# untitled.net
KiCad netlist of a schematic drawn in EAGLE
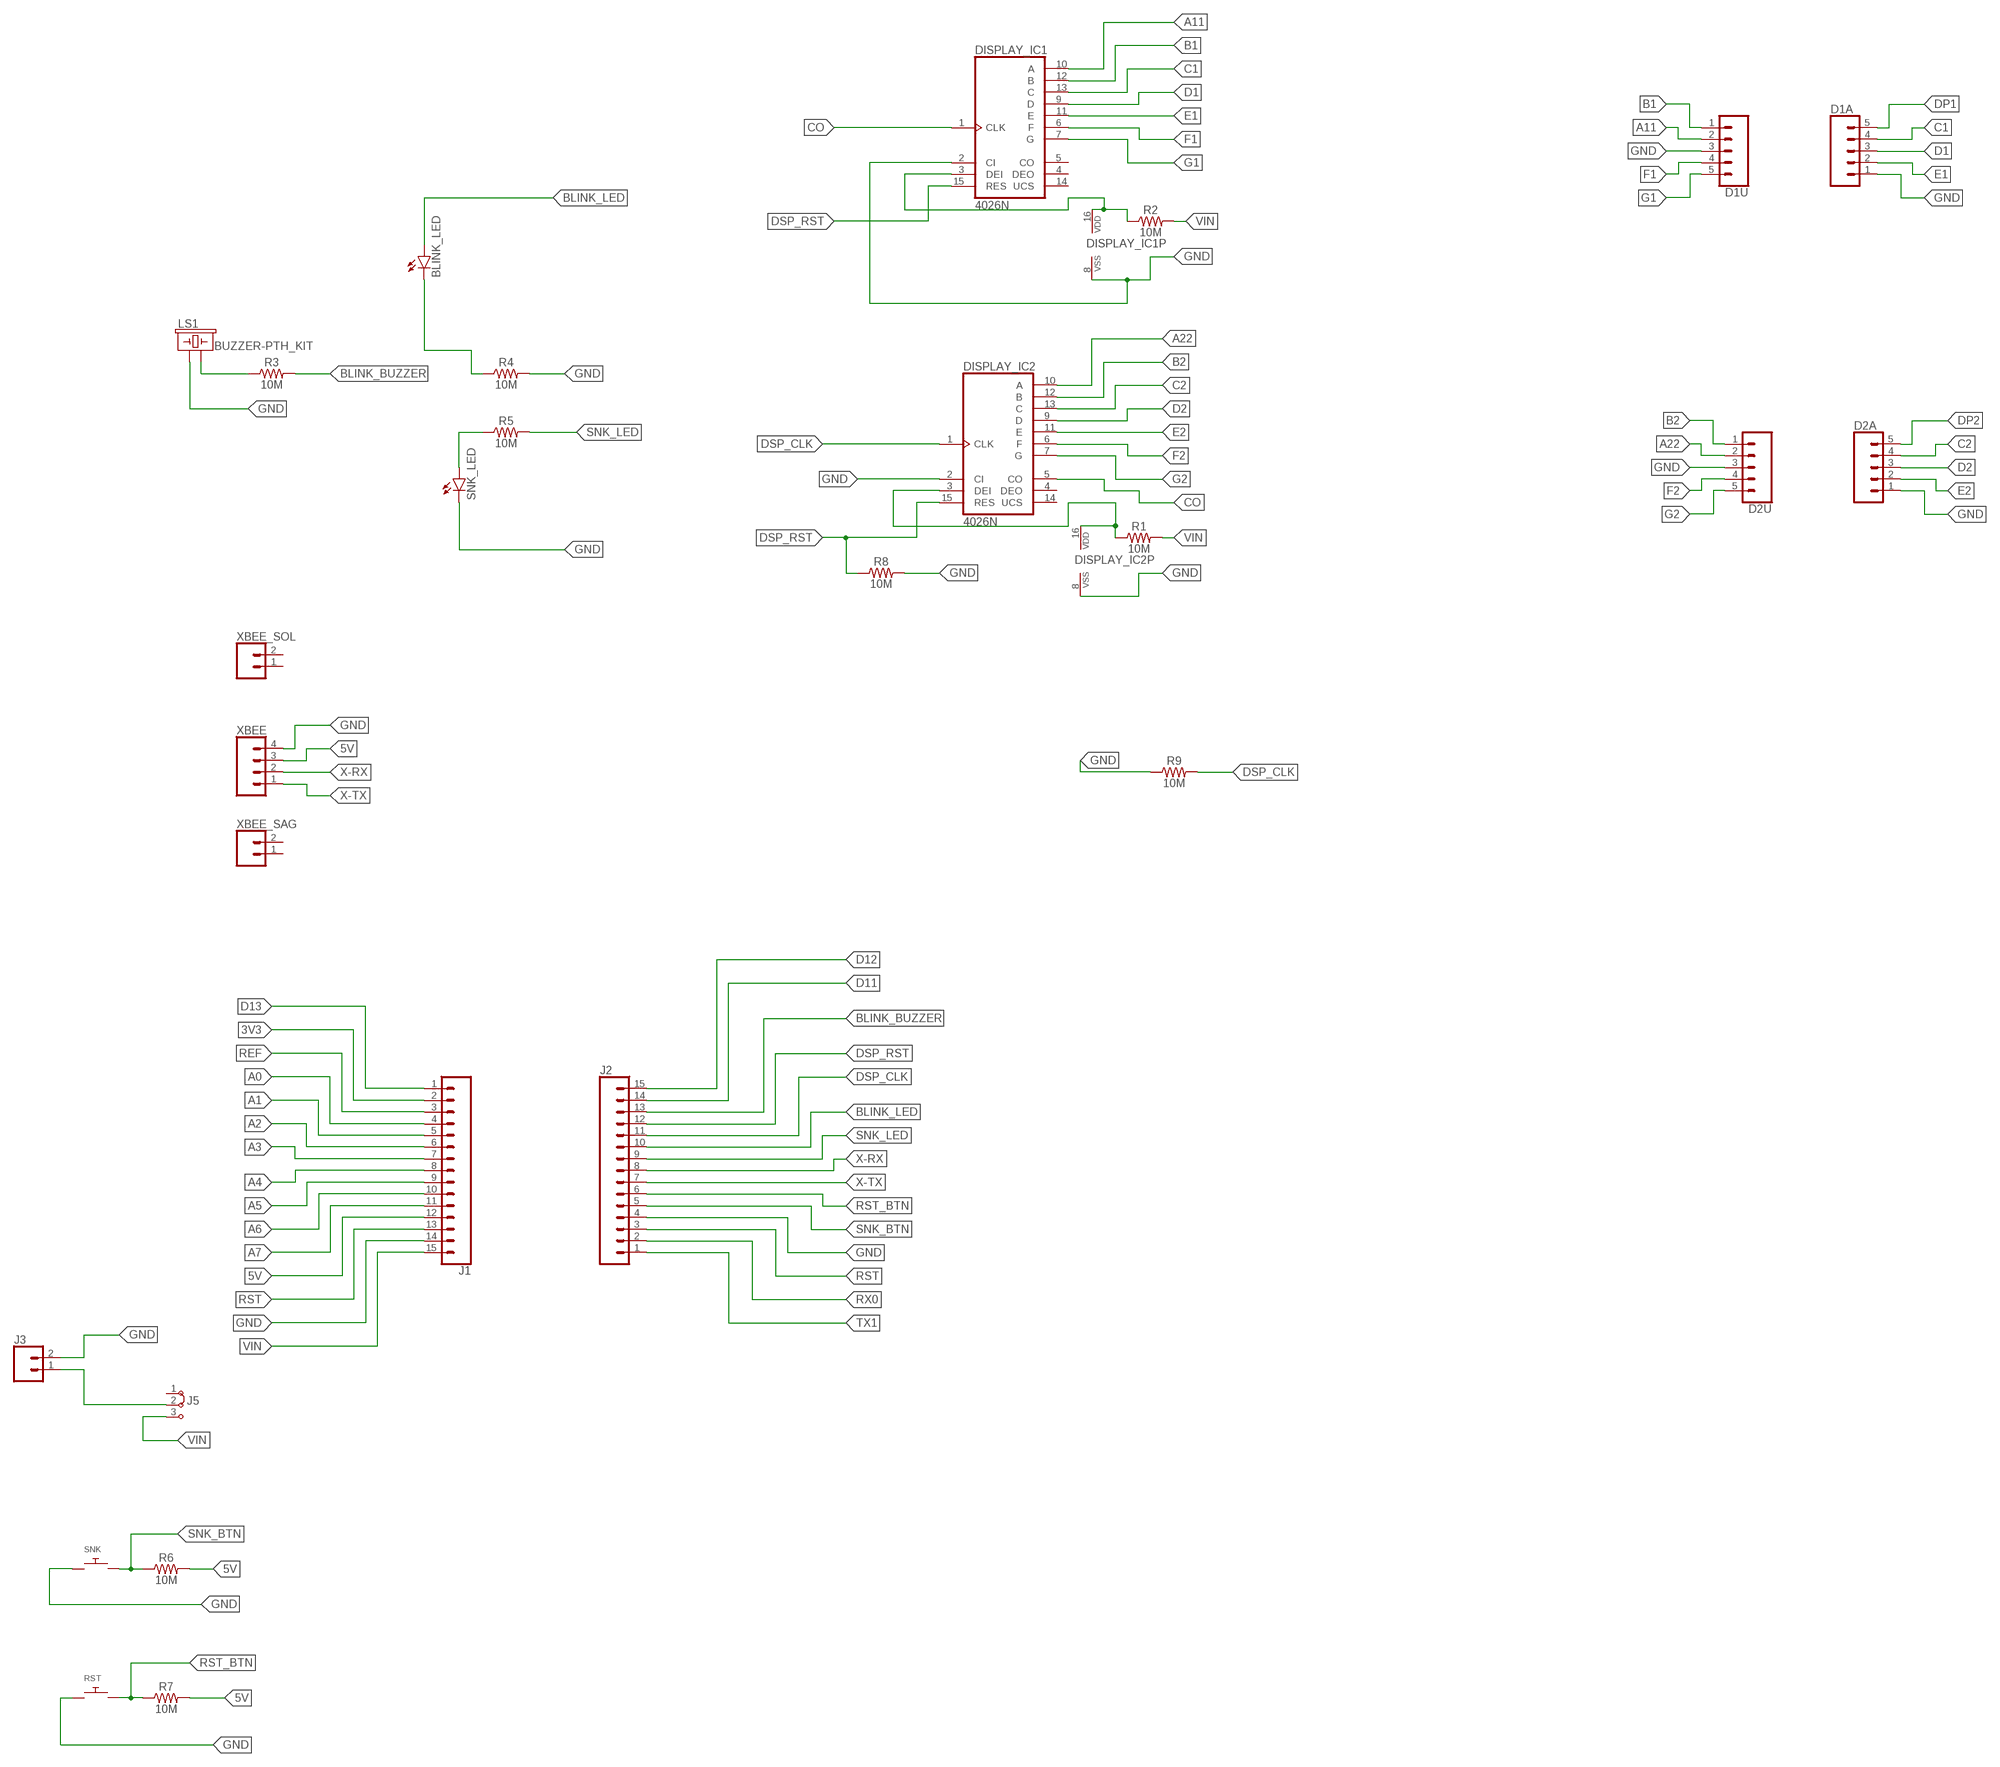
[diagram p0: schematic, sheet 1]

(export (version "E")
  (design (tool "Eeschema 10.0.6"))
  (components
    (comp (ref "BLINK_LED")
      (value "LED5MM")
      (footprint "eagle-import:LED5MM")
      (libsource (lib "eagle-import") (part "LED5MM"))
    )
    (comp (ref "D1A")
      (value "CONN_05")
      (footprint "eagle-import:1X05")
      (libsource (lib "eagle-import") (part "CONN_05"))
    )
    (comp (ref "D1U")
      (value "CONN_05")
      (footprint "eagle-import:1X05")
      (libsource (lib "eagle-import") (part "CONN_05"))
    )
    (comp (ref "D2A")
      (value "CONN_05")
      (footprint "eagle-import:1X05")
      (libsource (lib "eagle-import") (part "CONN_05"))
    )
    (comp (ref "D2U")
      (value "CONN_05")
      (footprint "eagle-import:1X05")
      (libsource (lib "eagle-import") (part "CONN_05"))
    )
    (comp (ref "DISPLAY_IC1")
      (value "4026N")
      (footprint "eagle-import:DIL16")
      (fields (field (name "SPICEPREFIX") "X"))
      (libsource (lib "eagle-import") (part "4026N"))
    )
    (comp (ref "DISPLAY_IC2")
      (value "4026N")
      (footprint "eagle-import:DIL16")
      (fields (field (name "SPICEPREFIX") "X"))
      (libsource (lib "eagle-import") (part "4026N"))
    )
    (comp (ref "J1")
      (value "CONN_15")
      (footprint "eagle-import:1X15")
      (libsource (lib "eagle-import") (part "CONN_15"))
    )
    (comp (ref "J2")
      (value "CONN_15")
      (footprint "eagle-import:1X15")
      (libsource (lib "eagle-import") (part "CONN_15"))
    )
    (comp (ref "J3")
      (value "CONN_025MM")
      (footprint "eagle-import:SCREWTERMINAL-5MM-2")
      (libsource (lib "eagle-import") (part "CONN_025MM"))
    )
    (comp (ref "J5")
      (value "J2X2MM")
      (footprint "eagle-import:04C")
      (libsource (lib "eagle-import") (part "J2X2MM"))
    )
    (comp (ref "LS1")
      (value "BUZZER-PTH_KIT")
      (footprint "eagle-import:BUZZER-12MM-KIT")
      (libsource (lib "eagle-import") (part "BUZZER-PTH_KIT"))
    )
    (comp (ref "R1")
      (value "10M")
      (footprint "eagle-import:AXIAL-0.3")
      (libsource (lib "eagle-import") (part "10MOHM-HORIZ-1/4W-5%"))
    )
    (comp (ref "R2")
      (value "10M")
      (footprint "eagle-import:AXIAL-0.3")
      (libsource (lib "eagle-import") (part "10MOHM-HORIZ-1/4W-5%"))
    )
    (comp (ref "R3")
      (value "10M")
      (footprint "eagle-import:AXIAL-0.3")
      (libsource (lib "eagle-import") (part "10MOHM-HORIZ-1/4W-5%"))
    )
    (comp (ref "R4")
      (value "10M")
      (footprint "eagle-import:AXIAL-0.3")
      (libsource (lib "eagle-import") (part "10MOHM-HORIZ-1/4W-5%"))
    )
    (comp (ref "R5")
      (value "10M")
      (footprint "eagle-import:AXIAL-0.3")
      (libsource (lib "eagle-import") (part "10MOHM-HORIZ-1/4W-5%"))
    )
    (comp (ref "R6")
      (value "10M")
      (footprint "eagle-import:AXIAL-0.3")
      (libsource (lib "eagle-import") (part "10MOHM-HORIZ-1/4W-5%"))
    )
    (comp (ref "R7")
      (value "10M")
      (footprint "eagle-import:AXIAL-0.3")
      (libsource (lib "eagle-import") (part "10MOHM-HORIZ-1/4W-5%"))
    )
    (comp (ref "R8")
      (value "10M")
      (footprint "eagle-import:AXIAL-0.3")
      (libsource (lib "eagle-import") (part "10MOHM-HORIZ-1/4W-5%"))
    )
    (comp (ref "R9")
      (value "10M")
      (footprint "eagle-import:AXIAL-0.3")
      (libsource (lib "eagle-import") (part "10MOHM-HORIZ-1/4W-5%"))
    )
    (comp (ref "RST")
      (value "SWITCH_PUSHBUTTONEVQ-PE")
      (footprint "eagle-import:TACT_PANA-EVQ")
      (libsource (lib "eagle-import") (part "SWITCH_PUSHBUTTONEVQ-PE"))
    )
    (comp (ref "SNK")
      (value "SWITCH_PUSHBUTTONEVQ-PE")
      (footprint "eagle-import:TACT_PANA-EVQ")
      (libsource (lib "eagle-import") (part "SWITCH_PUSHBUTTONEVQ-PE"))
    )
    (comp (ref "SNK_LED")
      (value "LED5MM")
      (footprint "eagle-import:LED5MM")
      (libsource (lib "eagle-import") (part "LED5MM"))
    )
    (comp (ref "XBEE")
      (value "CONN_04")
      (footprint "eagle-import:1X04")
      (libsource (lib "eagle-import") (part "CONN_04"))
    )
    (comp (ref "XBEE_SAG")
      (value "CONN_02")
      (footprint "eagle-import:1X02")
      (libsource (lib "eagle-import") (part "CONN_02"))
    )
    (comp (ref "XBEE_SOL")
      (value "CONN_02")
      (footprint "eagle-import:1X02")
      (libsource (lib "eagle-import") (part "CONN_02"))
    )
  )
  (nets
    (net (code "1") (name "3V3") (class "Default")
      (node (ref "J1") (pin "2") (pinfunction "2_2") (pintype "passive"))
    )
    (net (code "2") (name "5V") (class "Default")
      (node (ref "J1") (pin "12") (pinfunction "12_12") (pintype "passive"))
      (node (ref "R6") (pin "P$2") (pinfunction "2_P$2") (pintype "passive"))
      (node (ref "R7") (pin "P$2") (pinfunction "2_P$2") (pintype "passive"))
      (node (ref "XBEE") (pin "3") (pinfunction "3_3") (pintype "passive"))
    )
    (net (code "3") (name "A0") (class "Default")
      (node (ref "J1") (pin "4") (pinfunction "4_4") (pintype "passive"))
    )
    (net (code "4") (name "A1") (class "Default")
      (node (ref "J1") (pin "5") (pinfunction "5_5") (pintype "passive"))
    )
    (net (code "5") (name "A2") (class "Default")
      (node (ref "J1") (pin "6") (pinfunction "6_6") (pintype "passive"))
    )
    (net (code "6") (name "A3") (class "Default")
      (node (ref "J1") (pin "7") (pinfunction "7_7") (pintype "passive"))
    )
    (net (code "7") (name "A4") (class "Default")
      (node (ref "J1") (pin "8") (pinfunction "8_8") (pintype "passive"))
    )
    (net (code "8") (name "A5") (class "Default")
      (node (ref "J1") (pin "9") (pinfunction "9_9") (pintype "passive"))
    )
    (net (code "9") (name "A6") (class "Default")
      (node (ref "J1") (pin "10") (pinfunction "10_10") (pintype "passive"))
    )
    (net (code "10") (name "A7") (class "Default")
      (node (ref "J1") (pin "11") (pinfunction "11_11") (pintype "passive"))
    )
    (net (code "11") (name "A11") (class "Default")
      (node (ref "D1U") (pin "2") (pinfunction "2_2") (pintype "passive"))
      (node (ref "DISPLAY_IC1") (pin "10") (pinfunction "A_10") (pintype "output"))
    )
    (net (code "12") (name "A22") (class "Default")
      (node (ref "D2U") (pin "2") (pinfunction "2_2") (pintype "passive"))
      (node (ref "DISPLAY_IC2") (pin "10") (pinfunction "A_10") (pintype "output"))
    )
    (net (code "13") (name "B1") (class "Default")
      (node (ref "D1U") (pin "1") (pinfunction "1_1") (pintype "passive"))
      (node (ref "DISPLAY_IC1") (pin "12") (pinfunction "B_12") (pintype "output"))
    )
    (net (code "14") (name "B2") (class "Default")
      (node (ref "D2U") (pin "1") (pinfunction "1_1") (pintype "passive"))
      (node (ref "DISPLAY_IC2") (pin "12") (pinfunction "B_12") (pintype "output"))
    )
    (net (code "15") (name "BLINK_BUZZER") (class "Default")
      (node (ref "J2") (pin "13") (pinfunction "13_13") (pintype "passive"))
      (node (ref "R3") (pin "P$2") (pinfunction "2_P$2") (pintype "passive"))
    )
    (net (code "16") (name "BLINK_LED") (class "Default")
      (node (ref "BLINK_LED") (pin "A") (pinfunction "A_A") (pintype "passive"))
      (node (ref "J2") (pin "10") (pinfunction "10_10") (pintype "passive"))
    )
    (net (code "17") (name "C1") (class "Default")
      (node (ref "D1A") (pin "4") (pinfunction "4_4") (pintype "passive"))
      (node (ref "DISPLAY_IC1") (pin "13") (pinfunction "C_13") (pintype "output"))
    )
    (net (code "18") (name "C2") (class "Default")
      (node (ref "D2A") (pin "4") (pinfunction "4_4") (pintype "passive"))
      (node (ref "DISPLAY_IC2") (pin "13") (pinfunction "C_13") (pintype "output"))
    )
    (net (code "19") (name "CO") (class "Default")
      (node (ref "DISPLAY_IC1") (pin "1") (pinfunction "CLK_1") (pintype "input"))
      (node (ref "DISPLAY_IC2") (pin "5") (pinfunction "CO_5") (pintype "output"))
    )
    (net (code "20") (name "D1") (class "Default")
      (node (ref "D1A") (pin "3") (pinfunction "3_3") (pintype "passive"))
      (node (ref "DISPLAY_IC1") (pin "9") (pinfunction "D_9") (pintype "output"))
    )
    (net (code "21") (name "D2") (class "Default")
      (node (ref "D2A") (pin "3") (pinfunction "3_3") (pintype "passive"))
      (node (ref "DISPLAY_IC2") (pin "9") (pinfunction "D_9") (pintype "output"))
    )
    (net (code "22") (name "D11") (class "Default")
      (node (ref "J2") (pin "14") (pinfunction "14_14") (pintype "passive"))
    )
    (net (code "23") (name "D12") (class "Default")
      (node (ref "J2") (pin "15") (pinfunction "15_15") (pintype "passive"))
    )
    (net (code "24") (name "D13") (class "Default")
      (node (ref "J1") (pin "1") (pinfunction "1_1") (pintype "passive"))
    )
    (net (code "25") (name "DP1") (class "Default")
      (node (ref "D1A") (pin "5") (pinfunction "5_5") (pintype "passive"))
    )
    (net (code "26") (name "DP2") (class "Default")
      (node (ref "D2A") (pin "5") (pinfunction "5_5") (pintype "passive"))
    )
    (net (code "27") (name "DSP_CLK") (class "Default")
      (node (ref "DISPLAY_IC2") (pin "1") (pinfunction "CLK_1") (pintype "input"))
      (node (ref "J2") (pin "11") (pinfunction "11_11") (pintype "passive"))
      (node (ref "R9") (pin "P$2") (pinfunction "2_P$2") (pintype "passive"))
    )
    (net (code "28") (name "DSP_RST") (class "Default")
      (node (ref "DISPLAY_IC1") (pin "15") (pinfunction "RES_15") (pintype "input"))
      (node (ref "DISPLAY_IC2") (pin "15") (pinfunction "RES_15") (pintype "input"))
      (node (ref "J2") (pin "12") (pinfunction "12_12") (pintype "passive"))
      (node (ref "R8") (pin "P$1") (pinfunction "1_P$1") (pintype "passive"))
    )
    (net (code "29") (name "E1") (class "Default")
      (node (ref "D1A") (pin "2") (pinfunction "2_2") (pintype "passive"))
      (node (ref "DISPLAY_IC1") (pin "11") (pinfunction "E_11") (pintype "output"))
    )
    (net (code "30") (name "E2") (class "Default")
      (node (ref "D2A") (pin "2") (pinfunction "2_2") (pintype "passive"))
      (node (ref "DISPLAY_IC2") (pin "11") (pinfunction "E_11") (pintype "output"))
    )
    (net (code "31") (name "F1") (class "Default")
      (node (ref "D1U") (pin "4") (pinfunction "4_4") (pintype "passive"))
      (node (ref "DISPLAY_IC1") (pin "6") (pinfunction "F_6") (pintype "output"))
    )
    (net (code "32") (name "F2") (class "Default")
      (node (ref "D2U") (pin "4") (pinfunction "4_4") (pintype "passive"))
      (node (ref "DISPLAY_IC2") (pin "6") (pinfunction "F_6") (pintype "output"))
    )
    (net (code "33") (name "G1") (class "Default")
      (node (ref "D1U") (pin "5") (pinfunction "5_5") (pintype "passive"))
      (node (ref "DISPLAY_IC1") (pin "7") (pinfunction "G_7") (pintype "output"))
    )
    (net (code "34") (name "G2") (class "Default")
      (node (ref "D2U") (pin "5") (pinfunction "5_5") (pintype "passive"))
      (node (ref "DISPLAY_IC2") (pin "7") (pinfunction "G_7") (pintype "output"))
    )
    (net (code "35") (name "GND") (class "Default")
      (node (ref "D1A") (pin "1") (pinfunction "1_1") (pintype "passive"))
      (node (ref "D1U") (pin "3") (pinfunction "3_3") (pintype "passive"))
      (node (ref "D2A") (pin "1") (pinfunction "1_1") (pintype "passive"))
      (node (ref "D2U") (pin "3") (pinfunction "3_3") (pintype "passive"))
      (node (ref "DISPLAY_IC1") (pin "2") (pinfunction "CI_2") (pintype "input"))
      (node (ref "DISPLAY_IC1") (pin "8") (pinfunction "VSS_8") (pintype "power_in"))
      (node (ref "DISPLAY_IC2") (pin "2") (pinfunction "CI_2") (pintype "input"))
      (node (ref "DISPLAY_IC2") (pin "8") (pinfunction "VSS_8") (pintype "power_in"))
      (node (ref "J1") (pin "14") (pinfunction "14_14") (pintype "passive"))
      (node (ref "J2") (pin "4") (pinfunction "4_4") (pintype "passive"))
      (node (ref "J3") (pin "2") (pinfunction "2_2") (pintype "passive"))
      (node (ref "LS1") (pin "+") (pinfunction "1_+") (pintype "passive"))
      (node (ref "R4") (pin "P$2") (pinfunction "2_P$2") (pintype "passive"))
      (node (ref "R8") (pin "P$2") (pinfunction "2_P$2") (pintype "passive"))
      (node (ref "R9") (pin "P$1") (pinfunction "1_P$1") (pintype "passive"))
      (node (ref "RST") (pin "P$1") (pinfunction "P$1_P$1") (pintype "passive"))
      (node (ref "SNK") (pin "P$1") (pinfunction "P$1_P$1") (pintype "passive"))
      (node (ref "SNK_LED") (pin "K") (pinfunction "C_K") (pintype "passive"))
      (node (ref "XBEE") (pin "4") (pinfunction "4_4") (pintype "passive"))
    )
    (net (code "36") (name "Net-(BLINK_LED-C)") (class "Default")
      (node (ref "BLINK_LED") (pin "K") (pinfunction "C_K") (pintype "passive"))
      (node (ref "R4") (pin "P$1") (pinfunction "1_P$1") (pintype "passive"))
    )
    (net (code "37") (name "Net-(DISPLAY_IC1A-DEI)") (class "Default")
      (node (ref "DISPLAY_IC1") (pin "16") (pinfunction "VDD_16") (pintype "power_in"))
      (node (ref "DISPLAY_IC1") (pin "3") (pinfunction "DEI_3") (pintype "input"))
      (node (ref "R2") (pin "P$1") (pinfunction "1_P$1") (pintype "passive"))
    )
    (net (code "38") (name "Net-(DISPLAY_IC2A-DEI)") (class "Default")
      (node (ref "DISPLAY_IC2") (pin "16") (pinfunction "VDD_16") (pintype "power_in"))
      (node (ref "DISPLAY_IC2") (pin "3") (pinfunction "DEI_3") (pintype "input"))
      (node (ref "R1") (pin "P$1") (pinfunction "1_P$1") (pintype "passive"))
    )
    (net (code "39") (name "Net-(J3-Pad1)") (class "Default")
      (node (ref "J3") (pin "1") (pinfunction "1_1") (pintype "passive"))
      (node (ref "J5") (pin "2") (pinfunction "2_2") (pintype "passive"))
    )
    (net (code "40") (name "Net-(LS1-2)") (class "Default")
      (node (ref "LS1") (pin "-") (pinfunction "2_-") (pintype "passive"))
      (node (ref "R3") (pin "P$1") (pinfunction "1_P$1") (pintype "passive"))
    )
    (net (code "41") (name "Net-(R5-1)") (class "Default")
      (node (ref "R5") (pin "P$1") (pinfunction "1_P$1") (pintype "passive"))
      (node (ref "SNK_LED") (pin "A") (pinfunction "A_A") (pintype "passive"))
    )
    (net (code "42") (name "REF") (class "Default")
      (node (ref "J1") (pin "3") (pinfunction "3_3") (pintype "passive"))
    )
    (net (code "43") (name "RST") (class "Default")
      (node (ref "J1") (pin "13") (pinfunction "13_13") (pintype "passive"))
      (node (ref "J2") (pin "3") (pinfunction "3_3") (pintype "passive"))
    )
    (net (code "44") (name "RST_BTN") (class "Default")
      (node (ref "J2") (pin "6") (pinfunction "6_6") (pintype "passive"))
      (node (ref "R7") (pin "P$1") (pinfunction "1_P$1") (pintype "passive"))
      (node (ref "RST") (pin "P$2") (pinfunction "P$2_P$2") (pintype "passive"))
    )
    (net (code "45") (name "RX0") (class "Default")
      (node (ref "J2") (pin "2") (pinfunction "2_2") (pintype "passive"))
    )
    (net (code "46") (name "SNK_BTN") (class "Default")
      (node (ref "J2") (pin "5") (pinfunction "5_5") (pintype "passive"))
      (node (ref "R6") (pin "P$1") (pinfunction "1_P$1") (pintype "passive"))
      (node (ref "SNK") (pin "P$2") (pinfunction "P$2_P$2") (pintype "passive"))
    )
    (net (code "47") (name "SNK_LED") (class "Default")
      (node (ref "J2") (pin "9") (pinfunction "9_9") (pintype "passive"))
      (node (ref "R5") (pin "P$2") (pinfunction "2_P$2") (pintype "passive"))
    )
    (net (code "48") (name "TX1") (class "Default")
      (node (ref "J2") (pin "1") (pinfunction "1_1") (pintype "passive"))
    )
    (net (code "49") (name "VIN") (class "Default")
      (node (ref "J1") (pin "15") (pinfunction "15_15") (pintype "passive"))
      (node (ref "J5") (pin "3") (pinfunction "3_3") (pintype "passive"))
      (node (ref "R1") (pin "P$2") (pinfunction "2_P$2") (pintype "passive"))
      (node (ref "R2") (pin "P$2") (pinfunction "2_P$2") (pintype "passive"))
    )
    (net (code "50") (name "X-RX") (class "Default")
      (node (ref "J2") (pin "8") (pinfunction "8_8") (pintype "passive"))
      (node (ref "XBEE") (pin "2") (pinfunction "2_2") (pintype "passive"))
    )
    (net (code "51") (name "X-TX") (class "Default")
      (node (ref "J2") (pin "7") (pinfunction "7_7") (pintype "passive"))
      (node (ref "XBEE") (pin "1") (pinfunction "1_1") (pintype "passive"))
    )
    (net (code "52") (name "unconnected-(DISPLAY_IC1A-CO-Pad5)") (class "Default")
      (node (ref "DISPLAY_IC1") (pin "5") (pinfunction "CO_5") (pintype "output"))
    )
    (net (code "53") (name "unconnected-(DISPLAY_IC1A-DEO-Pad4)") (class "Default")
      (node (ref "DISPLAY_IC1") (pin "4") (pinfunction "DEO_4") (pintype "output"))
    )
    (net (code "54") (name "unconnected-(DISPLAY_IC1A-UCS-Pad14)") (class "Default")
      (node (ref "DISPLAY_IC1") (pin "14") (pinfunction "UCS_14") (pintype "output"))
    )
    (net (code "55") (name "unconnected-(DISPLAY_IC2A-DEO-Pad4)") (class "Default")
      (node (ref "DISPLAY_IC2") (pin "4") (pinfunction "DEO_4") (pintype "output"))
    )
    (net (code "56") (name "unconnected-(DISPLAY_IC2A-UCS-Pad14)") (class "Default")
      (node (ref "DISPLAY_IC2") (pin "14") (pinfunction "UCS_14") (pintype "output"))
    )
    (net (code "57") (name "unconnected-(J5-Pad1)") (class "Default")
      (node (ref "J5") (pin "1") (pinfunction "1_1") (pintype "passive"))
    )
    (net (code "58") (name "unconnected-(XBEE_SAG-Pad1)") (class "Default")
      (node (ref "XBEE_SAG") (pin "1") (pinfunction "1_1") (pintype "passive"))
    )
    (net (code "59") (name "unconnected-(XBEE_SAG-Pad2)") (class "Default")
      (node (ref "XBEE_SAG") (pin "2") (pinfunction "2_2") (pintype "passive"))
    )
    (net (code "60") (name "unconnected-(XBEE_SOL-Pad1)") (class "Default")
      (node (ref "XBEE_SOL") (pin "1") (pinfunction "1_1") (pintype "passive"))
    )
    (net (code "61") (name "unconnected-(XBEE_SOL-Pad2)") (class "Default")
      (node (ref "XBEE_SOL") (pin "2") (pinfunction "2_2") (pintype "passive"))
    )
  )
)
